# IMU_level_shifter.net
KiCad netlist of a schematic drawn in Altium Designer
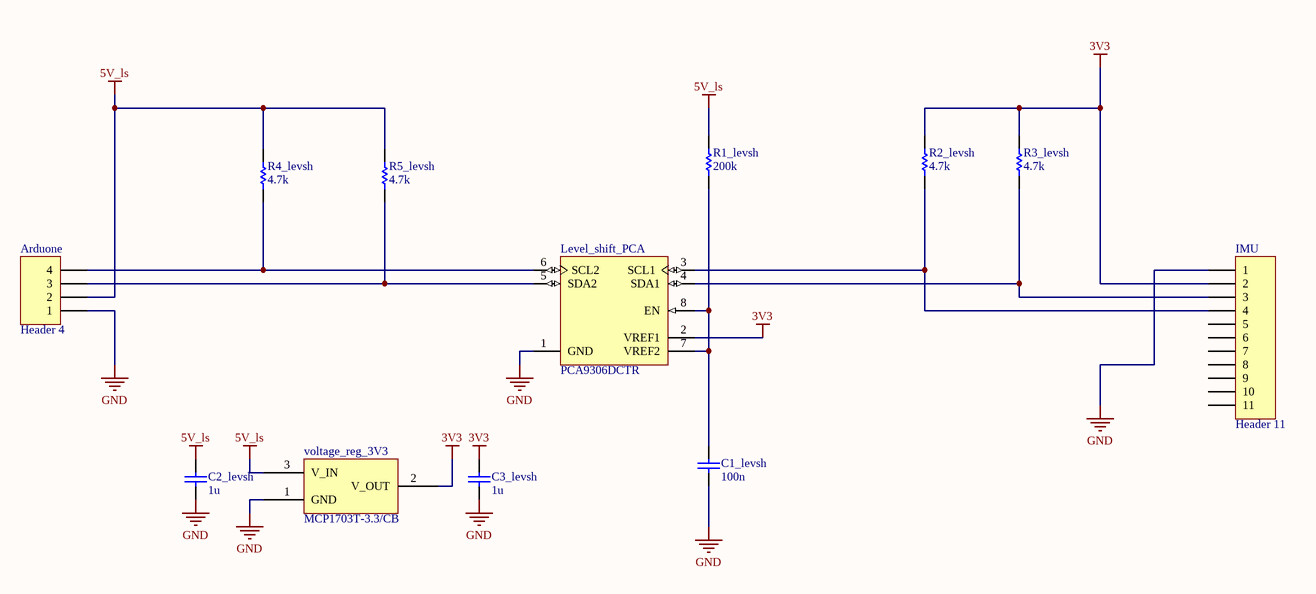
[diagram p0: IMU_level_shifter.SchDoc]

(export (version "E")
  (design (tool "Eeschema 10.0.6"))
  (components
    (comp (ref "Arduone")
      (value "Header 4")
      (footprint "HDR1X4")
      (description "Header, 4-Pin")
      (fields (field (name "PUBLISHER") "Altium Limited"))
      (libsource (lib "Miscellaneous Connectors") (part "Header 4"))
    )
    (comp (ref "C1_levsh")
      (value "100n")
      (footprint "CAPC1608N")
      (description "Capacitor")
      (fields (field (name "PUBLISHER") "Altium Limited"))
      (libsource (lib "Miscellaneous Devices") (part "Cap"))
    )
    (comp (ref "C2_levsh")
      (value "1u")
      (footprint "CAPC1608N")
      (description "Capacitor")
      (fields (field (name "PUBLISHER") "Altium Limited"))
      (libsource (lib "Miscellaneous Devices") (part "Cap"))
    )
    (comp (ref "C3_levsh")
      (value "1u")
      (footprint "CAPC1608N")
      (description "Capacitor")
      (fields (field (name "PUBLISHER") "Altium Limited"))
      (libsource (lib "Miscellaneous Devices") (part "Cap"))
    )
    (comp (ref "IMU")
      (value "Header 11")
      (footprint "HDR1X11")
      (description "Header, 11-Pin")
      (fields (field (name "PUBLISHER") "Altium Limited"))
      (libsource (lib "Miscellaneous Connectors") (part "Header 11"))
    )
    (comp (ref "Level_shift_PCA")
      (value "PCA9306DCTR")
      (footprint "DCT8_N")
      (fields (field (name "MANUFACTURER") "Texas Instruments"))
      (libsource (lib "Texas Instruments Interface I2C") (part "PCA9306DCTR"))
    )
    (comp (ref "R1_levsh")
      (value "200k")
      (footprint "RESC1608N")
      (description "Resistor")
      (fields (field (name "PUBLISHER") "Altium Limited"))
      (libsource (lib "Miscellaneous Devices") (part "Res1"))
    )
    (comp (ref "R2_levsh")
      (value "4.7k")
      (footprint "RESC1608N")
      (description "Resistor")
      (fields (field (name "PUBLISHER") "Altium Limited"))
      (libsource (lib "Miscellaneous Devices") (part "Res1"))
    )
    (comp (ref "R3_levsh")
      (value "4.7k")
      (footprint "RESC1608N")
      (description "Resistor")
      (fields (field (name "PUBLISHER") "Altium Limited"))
      (libsource (lib "Miscellaneous Devices") (part "Res1"))
    )
    (comp (ref "R4_levsh")
      (value "4.7k")
      (footprint "RESC1608N")
      (description "Resistor")
      (fields (field (name "PUBLISHER") "Altium Limited"))
      (libsource (lib "Miscellaneous Devices") (part "Res1"))
    )
    (comp (ref "R5_levsh")
      (value "4.7k")
      (footprint "RESC1608N")
      (description "Resistor")
      (fields (field (name "PUBLISHER") "Altium Limited"))
      (libsource (lib "Miscellaneous Devices") (part "Res1"))
    )
    (comp (ref "voltage_reg_3V3")
      (value "MCP1703T-3.3/CB")
      (footprint "SOT23-3N")
      (description "250 mA, 16V, Low Quiescent Current LDO Regulator")
      (libsource (lib "Ale") (part "MCP1703T/CB"))
    )
  )
  (nets
    (net (code "1") (name "3V3") (class "Default")
      (node (ref "C3_levsh") (pin "2") (pinfunction "2_2") (pintype "passive"))
      (node (ref "IMU") (pin "2") (pinfunction "2_2") (pintype "passive"))
      (node (ref "Level_shift_PCA") (pin "2") (pinfunction "VREF1_2") (pintype "power_in"))
      (node (ref "R2_levsh") (pin "2") (pinfunction "2_2") (pintype "passive"))
      (node (ref "R3_levsh") (pin "2") (pinfunction "2_2") (pintype "passive"))
      (node (ref "voltage_reg_3V3") (pin "2") (pinfunction "V_OUT_2") (pintype "power_in"))
    )
    (net (code "2") (name "5V_ls") (class "Default")
      (node (ref "Arduone") (pin "2") (pinfunction "2_2") (pintype "passive"))
      (node (ref "C2_levsh") (pin "2") (pinfunction "2_2") (pintype "passive"))
      (node (ref "R1_levsh") (pin "1") (pinfunction "1_1") (pintype "passive"))
      (node (ref "R4_levsh") (pin "2") (pinfunction "2_2") (pintype "passive"))
      (node (ref "R5_levsh") (pin "2") (pinfunction "2_2") (pintype "passive"))
      (node (ref "voltage_reg_3V3") (pin "3") (pinfunction "V_IN_3") (pintype "power_in"))
    )
    (net (code "3") (name "GND") (class "Default")
      (node (ref "Arduone") (pin "1") (pinfunction "1_1") (pintype "passive"))
      (node (ref "C1_levsh") (pin "1") (pinfunction "1_1") (pintype "passive"))
      (node (ref "C2_levsh") (pin "1") (pinfunction "1_1") (pintype "passive"))
      (node (ref "C3_levsh") (pin "1") (pinfunction "1_1") (pintype "passive"))
      (node (ref "IMU") (pin "1") (pinfunction "1_1") (pintype "passive"))
      (node (ref "Level_shift_PCA") (pin "1") (pinfunction "GND_1") (pintype "power_in"))
      (node (ref "voltage_reg_3V3") (pin "1") (pinfunction "GND_1") (pintype "power_in"))
    )
    (net (code "4") (name "Net-(Level_shift_PCA-EN)") (class "Default")
      (node (ref "C1_levsh") (pin "2") (pinfunction "2_2") (pintype "passive"))
      (node (ref "Level_shift_PCA") (pin "7") (pinfunction "VREF2_7") (pintype "power_in"))
      (node (ref "Level_shift_PCA") (pin "8") (pinfunction "EN_8") (pintype "input"))
      (node (ref "R1_levsh") (pin "2") (pinfunction "2_2") (pintype "passive"))
    )
    (net (code "5") (name "Net-(Level_shift_PCA-SCL1)") (class "Default")
      (node (ref "IMU") (pin "4") (pinfunction "4_4") (pintype "passive"))
      (node (ref "Level_shift_PCA") (pin "3") (pinfunction "SCL1_3") (pintype "bidirectional"))
      (node (ref "R2_levsh") (pin "1") (pinfunction "1_1") (pintype "passive"))
    )
    (net (code "6") (name "Net-(Level_shift_PCA-SCL2)") (class "Default")
      (node (ref "Arduone") (pin "4") (pinfunction "4_4") (pintype "passive"))
      (node (ref "Level_shift_PCA") (pin "6") (pinfunction "SCL2_6") (pintype "bidirectional"))
      (node (ref "R4_levsh") (pin "1") (pinfunction "1_1") (pintype "passive"))
    )
    (net (code "7") (name "Net-(Level_shift_PCA-SDA1)") (class "Default")
      (node (ref "IMU") (pin "3") (pinfunction "3_3") (pintype "passive"))
      (node (ref "Level_shift_PCA") (pin "4") (pinfunction "SDA1_4") (pintype "bidirectional"))
      (node (ref "R3_levsh") (pin "1") (pinfunction "1_1") (pintype "passive"))
    )
    (net (code "8") (name "Net-(Level_shift_PCA-SDA2)") (class "Default")
      (node (ref "Arduone") (pin "3") (pinfunction "3_3") (pintype "passive"))
      (node (ref "Level_shift_PCA") (pin "5") (pinfunction "SDA2_5") (pintype "bidirectional"))
      (node (ref "R5_levsh") (pin "1") (pinfunction "1_1") (pintype "passive"))
    )
    (net (code "9") (name "unconnected-(IMU-Pad5)") (class "Default")
      (node (ref "IMU") (pin "5") (pinfunction "5_5") (pintype "passive"))
    )
    (net (code "10") (name "unconnected-(IMU-Pad6)") (class "Default")
      (node (ref "IMU") (pin "6") (pinfunction "6_6") (pintype "passive"))
    )
    (net (code "11") (name "unconnected-(IMU-Pad7)") (class "Default")
      (node (ref "IMU") (pin "7") (pinfunction "7_7") (pintype "passive"))
    )
    (net (code "12") (name "unconnected-(IMU-Pad8)") (class "Default")
      (node (ref "IMU") (pin "8") (pinfunction "8_8") (pintype "passive"))
    )
    (net (code "13") (name "unconnected-(IMU-Pad9)") (class "Default")
      (node (ref "IMU") (pin "9") (pinfunction "9_9") (pintype "passive"))
    )
    (net (code "14") (name "unconnected-(IMU-Pad10)") (class "Default")
      (node (ref "IMU") (pin "10") (pinfunction "10_10") (pintype "passive"))
    )
    (net (code "15") (name "unconnected-(IMU-Pad11)") (class "Default")
      (node (ref "IMU") (pin "11") (pinfunction "11_11") (pintype "passive"))
    )
  )
)
